# ModuleConnectorB.net
KiCad netlist of a schematic drawn in Altium Designer
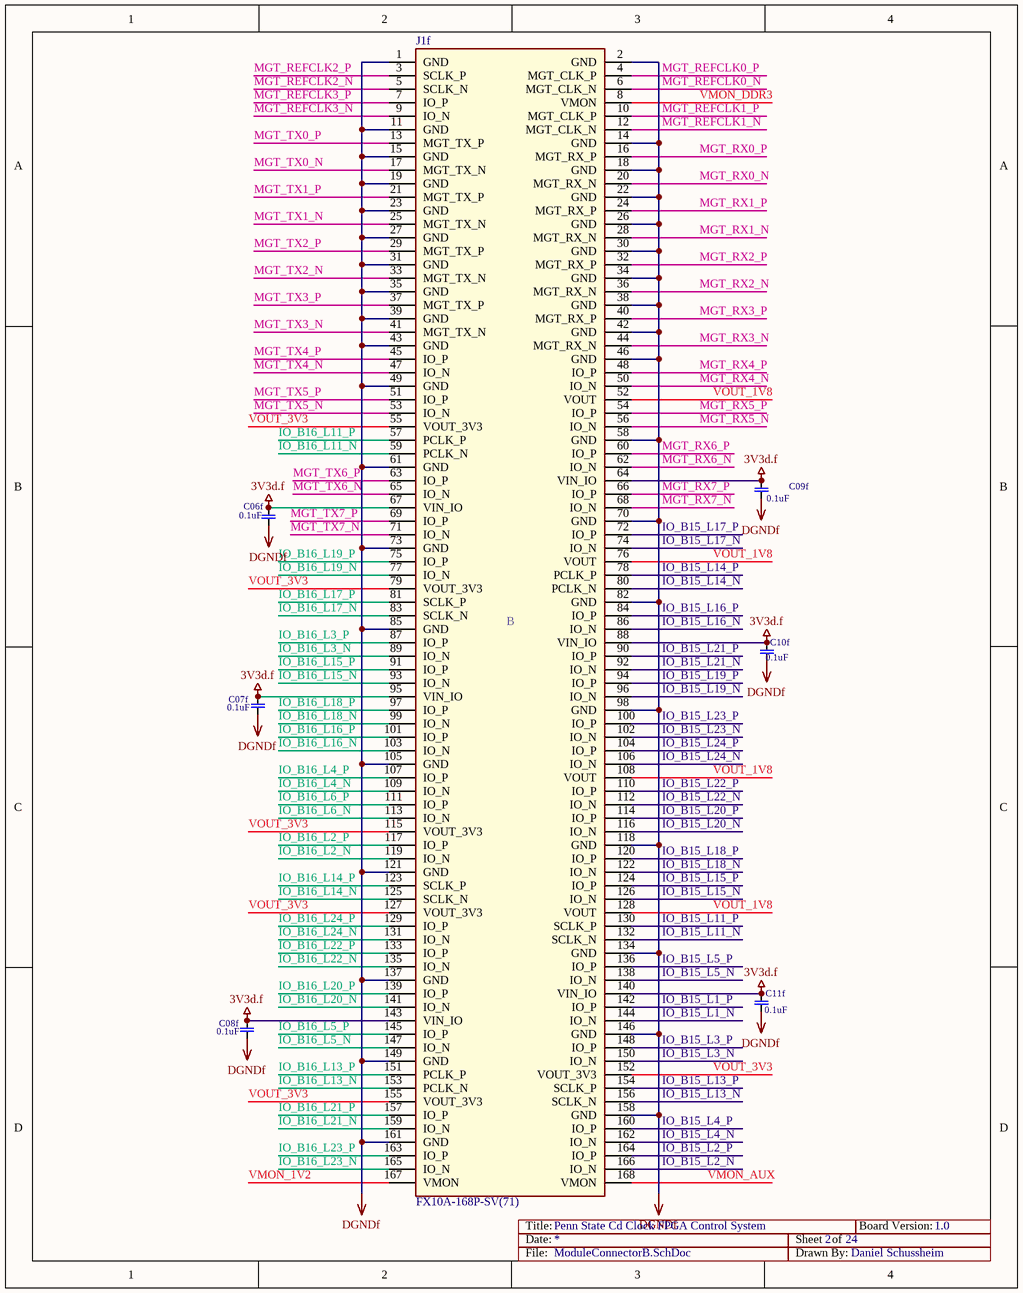
[diagram p0: ModuleConnectorB.SchDoc]

(export (version "E")
  (design (tool "Eeschema 10.0.6"))
  (components
    (comp (ref "C06f")
      (value "0.1uF")
      (footprint "0603")
      (libsource (lib "Mercury_AD_BaseBoard_SCHLIB") (part "CAP"))
    )
    (comp (ref "C07f")
      (value "0.1uF")
      (footprint "0603")
      (libsource (lib "Mercury_AD_BaseBoard_SCHLIB") (part "CAP"))
    )
    (comp (ref "C08f")
      (value "0.1uF")
      (footprint "0603")
      (libsource (lib "Mercury_AD_BaseBoard_SCHLIB") (part "CAP"))
    )
    (comp (ref "C09f")
      (value "0.1uF")
      (footprint "0603")
      (libsource (lib "Mercury_AD_BaseBoard_SCHLIB") (part "CAP"))
    )
    (comp (ref "C10f")
      (value "0.1uF")
      (footprint "0603")
      (libsource (lib "Mercury_AD_BaseBoard_SCHLIB") (part "CAP"))
    )
    (comp (ref "C11f")
      (value "0.1uF")
      (footprint "0603")
      (libsource (lib "Mercury_AD_BaseBoard_SCHLIB") (part "CAP"))
    )
    (comp (ref "J1f")
      (value "FX10A-168P-SV(71)")
      (footprint "Mercury_Baseboard_Connector")
      (description "Mercury Baseboard Connector")
      (fields
        (field (name "MANUFACTURER") "Hirose")
        (field (name "DISTPARTNUMBER") "FX10A-168P-SV(71)-ND")
        (field (name "CHECK SCH") "CG_2015-03-03")
      )
      (libsource (lib "Enclustra-Mars-Mercury-Altium-Library") (part "Mercury_Baseboard_Connector-B"))
    )
  )
  (nets
    (net (code "1") (name "/IO_B15_L1_N") (class "Default")
      (node (ref "J1f") (pin "144") (pinfunction "IO_N_144") (pintype "passive"))
    )
    (net (code "2") (name "/IO_B15_L1_P") (class "Default")
      (node (ref "J1f") (pin "142") (pinfunction "IO_P_142") (pintype "passive"))
    )
    (net (code "3") (name "/IO_B15_L2_N") (class "Default")
      (node (ref "J1f") (pin "166") (pinfunction "IO_N_166") (pintype "passive"))
    )
    (net (code "4") (name "/IO_B15_L2_P") (class "Default")
      (node (ref "J1f") (pin "164") (pinfunction "IO_P_164") (pintype "passive"))
    )
    (net (code "5") (name "/IO_B15_L3_N") (class "Default")
      (node (ref "J1f") (pin "150") (pinfunction "IO_N_150") (pintype "passive"))
    )
    (net (code "6") (name "/IO_B15_L3_P") (class "Default")
      (node (ref "J1f") (pin "148") (pinfunction "IO_P_148") (pintype "passive"))
    )
    (net (code "7") (name "/IO_B15_L4_N") (class "Default")
      (node (ref "J1f") (pin "162") (pinfunction "IO_N_162") (pintype "passive"))
    )
    (net (code "8") (name "/IO_B15_L4_P") (class "Default")
      (node (ref "J1f") (pin "160") (pinfunction "IO_P_160") (pintype "passive"))
    )
    (net (code "9") (name "/IO_B15_L5_N") (class "Default")
      (node (ref "J1f") (pin "138") (pinfunction "IO_N_138") (pintype "passive"))
    )
    (net (code "10") (name "/IO_B15_L5_P") (class "Default")
      (node (ref "J1f") (pin "136") (pinfunction "IO_P_136") (pintype "passive"))
    )
    (net (code "11") (name "/IO_B15_L11_N") (class "Default")
      (node (ref "J1f") (pin "132") (pinfunction "SCLK_N_132") (pintype "passive"))
    )
    (net (code "12") (name "/IO_B15_L11_P") (class "Default")
      (node (ref "J1f") (pin "130") (pinfunction "SCLK_P_130") (pintype "passive"))
    )
    (net (code "13") (name "/IO_B15_L13_N") (class "Default")
      (node (ref "J1f") (pin "156") (pinfunction "SCLK_N_156") (pintype "passive"))
    )
    (net (code "14") (name "/IO_B15_L13_P") (class "Default")
      (node (ref "J1f") (pin "154") (pinfunction "SCLK_P_154") (pintype "passive"))
    )
    (net (code "15") (name "/IO_B15_L14_N") (class "Default")
      (node (ref "J1f") (pin "80") (pinfunction "PCLK_N_80") (pintype "passive"))
    )
    (net (code "16") (name "/IO_B15_L14_P") (class "Default")
      (node (ref "J1f") (pin "78") (pinfunction "PCLK_P_78") (pintype "passive"))
    )
    (net (code "17") (name "/IO_B15_L15_N") (class "Default")
      (node (ref "J1f") (pin "126") (pinfunction "IO_N_126") (pintype "passive"))
    )
    (net (code "18") (name "/IO_B15_L15_P") (class "Default")
      (node (ref "J1f") (pin "124") (pinfunction "IO_P_124") (pintype "passive"))
    )
    (net (code "19") (name "/IO_B15_L16_N") (class "Default")
      (node (ref "J1f") (pin "86") (pinfunction "IO_N_86") (pintype "passive"))
    )
    (net (code "20") (name "/IO_B15_L16_P") (class "Default")
      (node (ref "J1f") (pin "84") (pinfunction "IO_P_84") (pintype "passive"))
    )
    (net (code "21") (name "/IO_B15_L17_N") (class "Default")
      (node (ref "J1f") (pin "74") (pinfunction "IO_N_74") (pintype "passive"))
    )
    (net (code "22") (name "/IO_B15_L17_P") (class "Default")
      (node (ref "J1f") (pin "72") (pinfunction "IO_P_72") (pintype "passive"))
    )
    (net (code "23") (name "/IO_B15_L18_N") (class "Default")
      (node (ref "J1f") (pin "122") (pinfunction "IO_N_122") (pintype "passive"))
    )
    (net (code "24") (name "/IO_B15_L18_P") (class "Default")
      (node (ref "J1f") (pin "120") (pinfunction "IO_P_120") (pintype "passive"))
    )
    (net (code "25") (name "/IO_B15_L19_N") (class "Default")
      (node (ref "J1f") (pin "96") (pinfunction "IO_N_96") (pintype "passive"))
    )
    (net (code "26") (name "/IO_B15_L19_P") (class "Default")
      (node (ref "J1f") (pin "94") (pinfunction "IO_P_94") (pintype "passive"))
    )
    (net (code "27") (name "/IO_B15_L20_N") (class "Default")
      (node (ref "J1f") (pin "116") (pinfunction "IO_N_116") (pintype "passive"))
    )
    (net (code "28") (name "/IO_B15_L20_P") (class "Default")
      (node (ref "J1f") (pin "114") (pinfunction "IO_P_114") (pintype "passive"))
    )
    (net (code "29") (name "/IO_B15_L21_N") (class "Default")
      (node (ref "J1f") (pin "92") (pinfunction "IO_N_92") (pintype "passive"))
    )
    (net (code "30") (name "/IO_B15_L21_P") (class "Default")
      (node (ref "J1f") (pin "90") (pinfunction "IO_P_90") (pintype "passive"))
    )
    (net (code "31") (name "/IO_B15_L22_N") (class "Default")
      (node (ref "J1f") (pin "112") (pinfunction "IO_N_112") (pintype "passive"))
    )
    (net (code "32") (name "/IO_B15_L22_P") (class "Default")
      (node (ref "J1f") (pin "110") (pinfunction "IO_P_110") (pintype "passive"))
    )
    (net (code "33") (name "/IO_B15_L23_N") (class "Default")
      (node (ref "J1f") (pin "102") (pinfunction "IO_N_102") (pintype "passive"))
    )
    (net (code "34") (name "/IO_B15_L23_P") (class "Default")
      (node (ref "J1f") (pin "100") (pinfunction "IO_P_100") (pintype "passive"))
    )
    (net (code "35") (name "/IO_B15_L24_N") (class "Default")
      (node (ref "J1f") (pin "106") (pinfunction "IO_N_106") (pintype "passive"))
    )
    (net (code "36") (name "/IO_B15_L24_P") (class "Default")
      (node (ref "J1f") (pin "104") (pinfunction "IO_P_104") (pintype "passive"))
    )
    (net (code "37") (name "/IO_B16_L2_N") (class "Default")
      (node (ref "J1f") (pin "119") (pinfunction "IO_N_119") (pintype "passive"))
    )
    (net (code "38") (name "/IO_B16_L2_P") (class "Default")
      (node (ref "J1f") (pin "117") (pinfunction "IO_P_117") (pintype "passive"))
    )
    (net (code "39") (name "/IO_B16_L3_N") (class "Default")
      (node (ref "J1f") (pin "89") (pinfunction "IO_N_89") (pintype "passive"))
    )
    (net (code "40") (name "/IO_B16_L3_P") (class "Default")
      (node (ref "J1f") (pin "87") (pinfunction "IO_P_87") (pintype "passive"))
    )
    (net (code "41") (name "/IO_B16_L4_N") (class "Default")
      (node (ref "J1f") (pin "109") (pinfunction "IO_N_109") (pintype "passive"))
    )
    (net (code "42") (name "/IO_B16_L4_P") (class "Default")
      (node (ref "J1f") (pin "107") (pinfunction "IO_P_107") (pintype "passive"))
    )
    (net (code "43") (name "/IO_B16_L5_N") (class "Default")
      (node (ref "J1f") (pin "147") (pinfunction "IO_N_147") (pintype "passive"))
    )
    (net (code "44") (name "/IO_B16_L5_P") (class "Default")
      (node (ref "J1f") (pin "145") (pinfunction "IO_P_145") (pintype "passive"))
    )
    (net (code "45") (name "/IO_B16_L6_N") (class "Default")
      (node (ref "J1f") (pin "113") (pinfunction "IO_N_113") (pintype "passive"))
    )
    (net (code "46") (name "/IO_B16_L6_P") (class "Default")
      (node (ref "J1f") (pin "111") (pinfunction "IO_P_111") (pintype "passive"))
    )
    (net (code "47") (name "/IO_B16_L11_N") (class "Default")
      (node (ref "J1f") (pin "59") (pinfunction "PCLK_N_59") (pintype "passive"))
    )
    (net (code "48") (name "/IO_B16_L11_P") (class "Default")
      (node (ref "J1f") (pin "57") (pinfunction "PCLK_P_57") (pintype "passive"))
    )
    (net (code "49") (name "/IO_B16_L13_N") (class "Default")
      (node (ref "J1f") (pin "153") (pinfunction "PCLK_N_153") (pintype "passive"))
    )
    (net (code "50") (name "/IO_B16_L13_P") (class "Default")
      (node (ref "J1f") (pin "151") (pinfunction "PCLK_P_151") (pintype "passive"))
    )
    (net (code "51") (name "/IO_B16_L14_N") (class "Default")
      (node (ref "J1f") (pin "125") (pinfunction "SCLK_N_125") (pintype "passive"))
    )
    (net (code "52") (name "/IO_B16_L14_P") (class "Default")
      (node (ref "J1f") (pin "123") (pinfunction "SCLK_P_123") (pintype "passive"))
    )
    (net (code "53") (name "/IO_B16_L15_N") (class "Default")
      (node (ref "J1f") (pin "93") (pinfunction "IO_N_93") (pintype "passive"))
    )
    (net (code "54") (name "/IO_B16_L15_P") (class "Default")
      (node (ref "J1f") (pin "91") (pinfunction "IO_P_91") (pintype "passive"))
    )
    (net (code "55") (name "/IO_B16_L16_N") (class "Default")
      (node (ref "J1f") (pin "103") (pinfunction "IO_N_103") (pintype "passive"))
    )
    (net (code "56") (name "/IO_B16_L16_P") (class "Default")
      (node (ref "J1f") (pin "101") (pinfunction "IO_P_101") (pintype "passive"))
    )
    (net (code "57") (name "/IO_B16_L17_N") (class "Default")
      (node (ref "J1f") (pin "83") (pinfunction "SCLK_N_83") (pintype "passive"))
    )
    (net (code "58") (name "/IO_B16_L17_P") (class "Default")
      (node (ref "J1f") (pin "81") (pinfunction "SCLK_P_81") (pintype "passive"))
    )
    (net (code "59") (name "/IO_B16_L18_N") (class "Default")
      (node (ref "J1f") (pin "99") (pinfunction "IO_N_99") (pintype "passive"))
    )
    (net (code "60") (name "/IO_B16_L18_P") (class "Default")
      (node (ref "J1f") (pin "97") (pinfunction "IO_P_97") (pintype "passive"))
    )
    (net (code "61") (name "/IO_B16_L19_N") (class "Default")
      (node (ref "J1f") (pin "77") (pinfunction "IO_N_77") (pintype "passive"))
    )
    (net (code "62") (name "/IO_B16_L19_P") (class "Default")
      (node (ref "J1f") (pin "75") (pinfunction "IO_P_75") (pintype "passive"))
    )
    (net (code "63") (name "/IO_B16_L20_N") (class "Default")
      (node (ref "J1f") (pin "141") (pinfunction "IO_N_141") (pintype "passive"))
    )
    (net (code "64") (name "/IO_B16_L20_P") (class "Default")
      (node (ref "J1f") (pin "139") (pinfunction "IO_P_139") (pintype "passive"))
    )
    (net (code "65") (name "/IO_B16_L21_N") (class "Default")
      (node (ref "J1f") (pin "159") (pinfunction "IO_N_159") (pintype "passive"))
    )
    (net (code "66") (name "/IO_B16_L21_P") (class "Default")
      (node (ref "J1f") (pin "157") (pinfunction "IO_P_157") (pintype "passive"))
    )
    (net (code "67") (name "/IO_B16_L22_N") (class "Default")
      (node (ref "J1f") (pin "135") (pinfunction "IO_N_135") (pintype "passive"))
    )
    (net (code "68") (name "/IO_B16_L22_P") (class "Default")
      (node (ref "J1f") (pin "133") (pinfunction "IO_P_133") (pintype "passive"))
    )
    (net (code "69") (name "/IO_B16_L23_N") (class "Default")
      (node (ref "J1f") (pin "165") (pinfunction "IO_N_165") (pintype "passive"))
    )
    (net (code "70") (name "/IO_B16_L23_P") (class "Default")
      (node (ref "J1f") (pin "163") (pinfunction "IO_P_163") (pintype "passive"))
    )
    (net (code "71") (name "/IO_B16_L24_N") (class "Default")
      (node (ref "J1f") (pin "131") (pinfunction "IO_N_131") (pintype "passive"))
    )
    (net (code "72") (name "/IO_B16_L24_P") (class "Default")
      (node (ref "J1f") (pin "129") (pinfunction "IO_P_129") (pintype "passive"))
    )
    (net (code "73") (name "/MGT_REFCLK0_N") (class "Default")
      (node (ref "J1f") (pin "6") (pinfunction "MGT_CLK_N_6") (pintype "passive"))
    )
    (net (code "74") (name "/MGT_REFCLK0_P") (class "Default")
      (node (ref "J1f") (pin "4") (pinfunction "MGT_CLK_P_4") (pintype "passive"))
    )
    (net (code "75") (name "/MGT_REFCLK1_N") (class "Default")
      (node (ref "J1f") (pin "12") (pinfunction "MGT_CLK_N_12") (pintype "passive"))
    )
    (net (code "76") (name "/MGT_REFCLK1_P") (class "Default")
      (node (ref "J1f") (pin "10") (pinfunction "MGT_CLK_P_10") (pintype "passive"))
    )
    (net (code "77") (name "/MGT_REFCLK2_N") (class "Default")
      (node (ref "J1f") (pin "5") (pinfunction "SCLK_N_5") (pintype "passive"))
    )
    (net (code "78") (name "/MGT_REFCLK2_P") (class "Default")
      (node (ref "J1f") (pin "3") (pinfunction "SCLK_P_3") (pintype "passive"))
    )
    (net (code "79") (name "/MGT_REFCLK3_N") (class "Default")
      (node (ref "J1f") (pin "9") (pinfunction "IO_N_9") (pintype "passive"))
    )
    (net (code "80") (name "/MGT_REFCLK3_P") (class "Default")
      (node (ref "J1f") (pin "7") (pinfunction "IO_P_7") (pintype "passive"))
    )
    (net (code "81") (name "/MGT_RX0_N") (class "Default")
      (node (ref "J1f") (pin "20") (pinfunction "MGT_RX_N_20") (pintype "passive"))
    )
    (net (code "82") (name "/MGT_RX0_P") (class "Default")
      (node (ref "J1f") (pin "16") (pinfunction "MGT_RX_P_16") (pintype "passive"))
    )
    (net (code "83") (name "/MGT_RX1_N") (class "Default")
      (node (ref "J1f") (pin "28") (pinfunction "MGT_RX_N_28") (pintype "passive"))
    )
    (net (code "84") (name "/MGT_RX1_P") (class "Default")
      (node (ref "J1f") (pin "24") (pinfunction "MGT_RX_P_24") (pintype "passive"))
    )
    (net (code "85") (name "/MGT_RX2_N") (class "Default")
      (node (ref "J1f") (pin "36") (pinfunction "MGT_RX_N_36") (pintype "passive"))
    )
    (net (code "86") (name "/MGT_RX2_P") (class "Default")
      (node (ref "J1f") (pin "32") (pinfunction "MGT_RX_P_32") (pintype "passive"))
    )
    (net (code "87") (name "/MGT_RX3_N") (class "Default")
      (node (ref "J1f") (pin "44") (pinfunction "MGT_RX_N_44") (pintype "passive"))
    )
    (net (code "88") (name "/MGT_RX3_P") (class "Default")
      (node (ref "J1f") (pin "40") (pinfunction "MGT_RX_P_40") (pintype "passive"))
    )
    (net (code "89") (name "/MGT_RX4_N") (class "Default")
      (node (ref "J1f") (pin "50") (pinfunction "IO_N_50") (pintype "passive"))
    )
    (net (code "90") (name "/MGT_RX4_P") (class "Default")
      (node (ref "J1f") (pin "48") (pinfunction "IO_P_48") (pintype "passive"))
    )
    (net (code "91") (name "/MGT_RX5_N") (class "Default")
      (node (ref "J1f") (pin "56") (pinfunction "IO_N_56") (pintype "passive"))
    )
    (net (code "92") (name "/MGT_RX5_P") (class "Default")
      (node (ref "J1f") (pin "54") (pinfunction "IO_P_54") (pintype "passive"))
    )
    (net (code "93") (name "/MGT_RX6_N") (class "Default")
      (node (ref "J1f") (pin "62") (pinfunction "IO_N_62") (pintype "passive"))
    )
    (net (code "94") (name "/MGT_RX6_P") (class "Default")
      (node (ref "J1f") (pin "60") (pinfunction "IO_P_60") (pintype "passive"))
    )
    (net (code "95") (name "/MGT_RX7_N") (class "Default")
      (node (ref "J1f") (pin "68") (pinfunction "IO_N_68") (pintype "passive"))
    )
    (net (code "96") (name "/MGT_RX7_P") (class "Default")
      (node (ref "J1f") (pin "66") (pinfunction "IO_P_66") (pintype "passive"))
    )
    (net (code "97") (name "/MGT_TX0_N") (class "Default")
      (node (ref "J1f") (pin "17") (pinfunction "MGT_TX_N_17") (pintype "passive"))
    )
    (net (code "98") (name "/MGT_TX0_P") (class "Default")
      (node (ref "J1f") (pin "13") (pinfunction "MGT_TX_P_13") (pintype "passive"))
    )
    (net (code "99") (name "/MGT_TX1_N") (class "Default")
      (node (ref "J1f") (pin "25") (pinfunction "MGT_TX_N_25") (pintype "passive"))
    )
    (net (code "100") (name "/MGT_TX1_P") (class "Default")
      (node (ref "J1f") (pin "21") (pinfunction "MGT_TX_P_21") (pintype "passive"))
    )
    (net (code "101") (name "/MGT_TX2_N") (class "Default")
      (node (ref "J1f") (pin "33") (pinfunction "MGT_TX_N_33") (pintype "passive"))
    )
    (net (code "102") (name "/MGT_TX2_P") (class "Default")
      (node (ref "J1f") (pin "29") (pinfunction "MGT_TX_P_29") (pintype "passive"))
    )
    (net (code "103") (name "/MGT_TX3_N") (class "Default")
      (node (ref "J1f") (pin "41") (pinfunction "MGT_TX_N_41") (pintype "passive"))
    )
    (net (code "104") (name "/MGT_TX3_P") (class "Default")
      (node (ref "J1f") (pin "37") (pinfunction "MGT_TX_P_37") (pintype "passive"))
    )
    (net (code "105") (name "/MGT_TX4_N") (class "Default")
      (node (ref "J1f") (pin "47") (pinfunction "IO_N_47") (pintype "passive"))
    )
    (net (code "106") (name "/MGT_TX4_P") (class "Default")
      (node (ref "J1f") (pin "45") (pinfunction "IO_P_45") (pintype "passive"))
    )
    (net (code "107") (name "/MGT_TX5_N") (class "Default")
      (node (ref "J1f") (pin "53") (pinfunction "IO_N_53") (pintype "passive"))
    )
    (net (code "108") (name "/MGT_TX5_P") (class "Default")
      (node (ref "J1f") (pin "51") (pinfunction "IO_P_51") (pintype "passive"))
    )
    (net (code "109") (name "/MGT_TX6_N") (class "Default")
      (node (ref "J1f") (pin "65") (pinfunction "IO_N_65") (pintype "passive"))
    )
    (net (code "110") (name "/MGT_TX6_P") (class "Default")
      (node (ref "J1f") (pin "63") (pinfunction "IO_P_63") (pintype "passive"))
    )
    (net (code "111") (name "/MGT_TX7_N") (class "Default")
      (node (ref "J1f") (pin "71") (pinfunction "IO_N_71") (pintype "passive"))
    )
    (net (code "112") (name "/MGT_TX7_P") (class "Default")
      (node (ref "J1f") (pin "69") (pinfunction "IO_P_69") (pintype "passive"))
    )
    (net (code "113") (name "/VMON_1V2") (class "Default")
      (node (ref "J1f") (pin "167") (pinfunction "VMON_167") (pintype "passive"))
    )
    (net (code "114") (name "/VMON_AUX") (class "Default")
      (node (ref "J1f") (pin "168") (pinfunction "VMON_168") (pintype "passive"))
    )
    (net (code "115") (name "/VMON_DDR3") (class "Default")
      (node (ref "J1f") (pin "8") (pinfunction "VMON_8") (pintype "passive"))
    )
    (net (code "116") (name "/VOUT_1V8") (class "Default")
      (node (ref "J1f") (pin "108") (pinfunction "VOUT_108") (pintype "passive"))
      (node (ref "J1f") (pin "128") (pinfunction "VOUT_128") (pintype "passive"))
      (node (ref "J1f") (pin "52") (pinfunction "VOUT_52") (pintype "passive"))
      (node (ref "J1f") (pin "76") (pinfunction "VOUT_76") (pintype "passive"))
    )
    (net (code "117") (name "/VOUT_3V3") (class "Default")
      (node (ref "J1f") (pin "115") (pinfunction "VOUT_3V3_115") (pintype "passive"))
      (node (ref "J1f") (pin "127") (pinfunction "VOUT_3V3_127") (pintype "passive"))
      (node (ref "J1f") (pin "152") (pinfunction "VOUT_3V3_152") (pintype "passive"))
      (node (ref "J1f") (pin "155") (pinfunction "VOUT_3V3_155") (pintype "passive"))
      (node (ref "J1f") (pin "55") (pinfunction "VOUT_3V3_55") (pintype "passive"))
      (node (ref "J1f") (pin "79") (pinfunction "VOUT_3V3_79") (pintype "passive"))
    )
    (net (code "118") (name "3V3d.f") (class "Default")
      (node (ref "C06f") (pin "1") (pintype "passive"))
      (node (ref "C07f") (pin "1") (pintype "passive"))
      (node (ref "C08f") (pin "1") (pintype "passive"))
      (node (ref "C09f") (pin "1") (pintype "passive"))
      (node (ref "C10f") (pin "1") (pintype "passive"))
      (node (ref "C11f") (pin "1") (pintype "passive"))
      (node (ref "J1f") (pin "140") (pinfunction "VIN_IO_140") (pintype "passive"))
      (node (ref "J1f") (pin "143") (pinfunction "VIN_IO_143") (pintype "passive"))
      (node (ref "J1f") (pin "64") (pinfunction "VIN_IO_64") (pintype "passive"))
      (node (ref "J1f") (pin "67") (pinfunction "VIN_IO_67") (pintype "passive"))
      (node (ref "J1f") (pin "88") (pinfunction "VIN_IO_88") (pintype "passive"))
      (node (ref "J1f") (pin "95") (pinfunction "VIN_IO_95") (pintype "passive"))
    )
    (net (code "119") (name "DGNDf") (class "Default")
      (node (ref "C06f") (pin "2") (pintype "passive"))
      (node (ref "C07f") (pin "2") (pintype "passive"))
      (node (ref "C08f") (pin "2") (pintype "passive"))
      (node (ref "C09f") (pin "2") (pintype "passive"))
      (node (ref "C10f") (pin "2") (pintype "passive"))
      (node (ref "C11f") (pin "2") (pintype "passive"))
      (node (ref "J1f") (pin "1") (pinfunction "GND_1") (pintype "passive"))
      (node (ref "J1f") (pin "105") (pinfunction "GND_105") (pintype "passive"))
      (node (ref "J1f") (pin "11") (pinfunction "GND_11") (pintype "passive"))
      (node (ref "J1f") (pin "118") (pinfunction "GND_118") (pintype "passive"))
      (node (ref "J1f") (pin "121") (pinfunction "GND_121") (pintype "passive"))
      (node (ref "J1f") (pin "134") (pinfunction "GND_134") (pintype "passive"))
      (node (ref "J1f") (pin "137") (pinfunction "GND_137") (pintype "passive"))
      (node (ref "J1f") (pin "14") (pinfunction "GND_14") (pintype "passive"))
      (node (ref "J1f") (pin "146") (pinfunction "GND_146") (pintype "passive"))
      (node (ref "J1f") (pin "149") (pinfunction "GND_149") (pintype "passive"))
      (node (ref "J1f") (pin "15") (pinfunction "GND_15") (pintype "passive"))
      (node (ref "J1f") (pin "158") (pinfunction "GND_158") (pintype "passive"))
      (node (ref "J1f") (pin "161") (pinfunction "GND_161") (pintype "passive"))
      (node (ref "J1f") (pin "18") (pinfunction "GND_18") (pintype "passive"))
      (node (ref "J1f") (pin "19") (pinfunction "GND_19") (pintype "passive"))
      (node (ref "J1f") (pin "2") (pinfunction "GND_2") (pintype "passive"))
      (node (ref "J1f") (pin "22") (pinfunction "GND_22") (pintype "passive"))
      (node (ref "J1f") (pin "23") (pinfunction "GND_23") (pintype "passive"))
      (node (ref "J1f") (pin "26") (pinfunction "GND_26") (pintype "passive"))
      (node (ref "J1f") (pin "27") (pinfunction "GND_27") (pintype "passive"))
      (node (ref "J1f") (pin "30") (pinfunction "GND_30") (pintype "passive"))
      (node (ref "J1f") (pin "31") (pinfunction "GND_31") (pintype "passive"))
      (node (ref "J1f") (pin "34") (pinfunction "GND_34") (pintype "passive"))
      (node (ref "J1f") (pin "35") (pinfunction "GND_35") (pintype "passive"))
      (node (ref "J1f") (pin "38") (pinfunction "GND_38") (pintype "passive"))
      (node (ref "J1f") (pin "39") (pinfunction "GND_39") (pintype "passive"))
      (node (ref "J1f") (pin "42") (pinfunction "GND_42") (pintype "passive"))
      (node (ref "J1f") (pin "43") (pinfunction "GND_43") (pintype "passive"))
      (node (ref "J1f") (pin "46") (pinfunction "GND_46") (pintype "passive"))
      (node (ref "J1f") (pin "49") (pinfunction "GND_49") (pintype "passive"))
      (node (ref "J1f") (pin "58") (pinfunction "GND_58") (pintype "passive"))
      (node (ref "J1f") (pin "61") (pinfunction "GND_61") (pintype "passive"))
      (node (ref "J1f") (pin "70") (pinfunction "GND_70") (pintype "passive"))
      (node (ref "J1f") (pin "73") (pinfunction "GND_73") (pintype "passive"))
      (node (ref "J1f") (pin "82") (pinfunction "GND_82") (pintype "passive"))
      (node (ref "J1f") (pin "85") (pinfunction "GND_85") (pintype "passive"))
      (node (ref "J1f") (pin "98") (pinfunction "GND_98") (pintype "passive"))
    )
  )
)
